# v1_0.net
KiCad netlist of a schematic drawn in Altium Designer
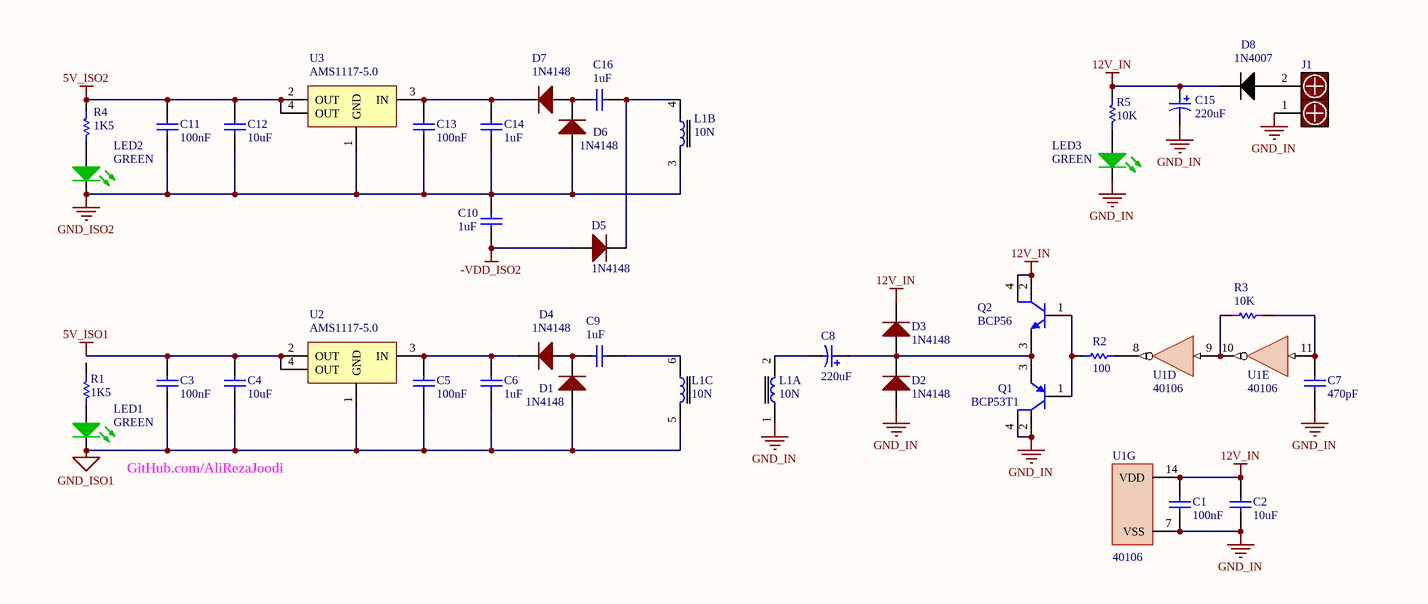
[diagram p0: v1.0.SchDoc]

(export (version "E")
  (design (tool "Eeschema 10.0.6"))
  (components
    (comp (ref "C1")
      (value "100nF")
      (footprint "Capacitor_Ceramic:SMD_0805")
      (description "Capacitor, Ceramic Multilayer, 25V, 10%")
      (libsource (lib "General") (part "Capacitor_Ceramic"))
    )
    (comp (ref "C2")
      (value "10uF")
      (footprint "Capacitor_Ceramic:SMD_0805")
      (description "Capacitor, Ceramic Multilayer, 25V, 10%")
      (libsource (lib "General") (part "Capacitor_Ceramic"))
    )
    (comp (ref "C3")
      (value "100nF")
      (footprint "Capacitor_Ceramic:SMD_0805")
      (description "Capacitor, Ceramic Multilayer, 25V, 10%")
      (libsource (lib "General") (part "Capacitor_Ceramic"))
    )
    (comp (ref "C4")
      (value "10uF")
      (footprint "Capacitor_Ceramic:SMD_0805")
      (description "Capacitor, Ceramic Multilayer, 25V, 10%")
      (libsource (lib "General") (part "Capacitor_Ceramic"))
    )
    (comp (ref "C5")
      (value "100nF")
      (footprint "Capacitor_Ceramic:SMD_0805")
      (description "Capacitor, Ceramic Multilayer, 25V, 10%")
      (libsource (lib "General") (part "Capacitor_Ceramic"))
    )
    (comp (ref "C6")
      (value "1uF")
      (footprint "Capacitor_Ceramic:SMD_0805")
      (description "Capacitor, Ceramic Multilayer, 25V, 10%")
      (libsource (lib "General") (part "Capacitor_Ceramic"))
    )
    (comp (ref "C7")
      (value "470pF")
      (footprint "Capacitor_Ceramic:SMD_0805")
      (description "Capacitor, Ceramic Multilayer, 25V, 10%")
      (libsource (lib "General") (part "Capacitor_Ceramic"))
    )
    (comp (ref "C8")
      (value "220uF")
      (footprint "THD_P3.4/D8/H12")
      (description "Capacitor, Electrolytic, 25V, 10%")
      (libsource (lib "General") (part "Capacitor_Electrolytic"))
    )
    (comp (ref "C9")
      (value "1uF")
      (footprint "Capacitor_Ceramic:SMD_0805")
      (description "Capacitor, Ceramic Multilayer, 25V, 10%")
      (libsource (lib "General") (part "Capacitor_Ceramic"))
    )
    (comp (ref "C10")
      (value "1uF")
      (footprint "Capacitor_Ceramic:SMD_0805")
      (description "Capacitor, Ceramic Multilayer, 25V, 10%")
      (libsource (lib "General") (part "Capacitor_Ceramic"))
    )
    (comp (ref "C11")
      (value "100nF")
      (footprint "Capacitor_Ceramic:SMD_0805")
      (description "Capacitor, Ceramic Multilayer, 25V, 10%")
      (libsource (lib "General") (part "Capacitor_Ceramic"))
    )
    (comp (ref "C12")
      (value "10uF")
      (footprint "Capacitor_Ceramic:SMD_0805")
      (description "Capacitor, Ceramic Multilayer, 25V, 10%")
      (libsource (lib "General") (part "Capacitor_Ceramic"))
    )
    (comp (ref "C13")
      (value "100nF")
      (footprint "Capacitor_Ceramic:SMD_0805")
      (description "Capacitor, Ceramic Multilayer, 25V, 10%")
      (libsource (lib "General") (part "Capacitor_Ceramic"))
    )
    (comp (ref "C14")
      (value "1uF")
      (footprint "Capacitor_Ceramic:SMD_0805")
      (description "Capacitor, Ceramic Multilayer, 25V, 10%")
      (libsource (lib "General") (part "Capacitor_Ceramic"))
    )
    (comp (ref "C15")
      (value "220uF")
      (footprint "THD_P3.4/D8/H12")
      (description "Capacitor, Electrolytic, 25V, 10%")
      (libsource (lib "General") (part "Capacitor_Electrolytic"))
    )
    (comp (ref "C16")
      (value "1uF")
      (footprint "Capacitor_Ceramic:SMD_0805")
      (description "Capacitor, Ceramic Multilayer, 25V, 10%")
      (libsource (lib "General") (part "Capacitor_Ceramic"))
    )
    (comp (ref "D1")
      (value "1N4148")
      (footprint "SMD_DO-213AA")
      (description "Diode")
      (fields (field (name "MANUFACTURER") "Microchip Technology") (field (name "PART NUMBER") "1N4148UR-1"))
      (libsource (lib "General") (part "Diode_2Form"))
    )
    (comp (ref "D2")
      (value "1N4148")
      (footprint "SMD_DO-213AA")
      (description "Diode")
      (fields (field (name "MANUFACTURER") "Microchip Technology") (field (name "PART NUMBER") "1N4148UR-1"))
      (libsource (lib "General") (part "Diode_2Form"))
    )
    (comp (ref "D3")
      (value "1N4148")
      (footprint "SMD_DO-213AA")
      (description "Diode")
      (fields (field (name "MANUFACTURER") "Microchip Technology") (field (name "PART NUMBER") "1N4148UR-1"))
      (libsource (lib "General") (part "Diode_2Form"))
    )
    (comp (ref "D4")
      (value "1N4148")
      (footprint "SMD_DO-213AA")
      (description "Diode")
      (fields (field (name "MANUFACTURER") "Microchip Technology") (field (name "PART NUMBER") "1N4148UR-1"))
      (libsource (lib "General") (part "Diode_2Form"))
    )
    (comp (ref "D5")
      (value "1N4148")
      (footprint "SMD_DO-213AA")
      (description "Diode")
      (fields (field (name "MANUFACTURER") "Microchip Technology") (field (name "PART NUMBER") "1N4148UR-1"))
      (libsource (lib "General") (part "Diode_2Form"))
    )
    (comp (ref "D6")
      (value "1N4148")
      (footprint "SMD_DO-213AA")
      (description "Diode")
      (fields (field (name "MANUFACTURER") "Microchip Technology") (field (name "PART NUMBER") "1N4148UR-1"))
      (libsource (lib "General") (part "Diode_2Form"))
    )
    (comp (ref "D7")
      (value "1N4148")
      (footprint "SMD_DO-213AA")
      (description "Diode")
      (fields (field (name "MANUFACTURER") "Microchip Technology") (field (name "PART NUMBER") "1N4148UR-1"))
      (libsource (lib "General") (part "Diode_2Form"))
    )
    (comp (ref "D8")
      (value "1N4007")
      (footprint "SMD_SOD123W")
      (description "Diode")
      (fields (field (name "MANUFACTURER") "SMC Diode Solutions") (field (name "PART NUMBER") "1N4007FL"))
      (libsource (lib "General") (part "Diode"))
    )
    (comp (ref "J1")
      (value "~")
      (footprint "1x2_P8.26")
      (description "Connector, Barrier Terminal Blocks, 2Pin")
      (fields (field (name "1_PART NUMBER") "1977477-2"))
      (libsource (lib "Connector") (part "Connector1x2_Power_4Form"))
    )
    (comp (ref "L1")
      (value "10N")
      (footprint "TOROIDS_DO25/DI15/L13")
      (description "Power Transformer, Ferrite Toroids")
      (fields (field (name "MANUFACTURER") "TDK") (field (name "PART NUMBER") "HF70T25X13X15"))
      (libsource (lib "") (part "Inductor_Trans_3Wire_2Form_1"))
    )
    (comp (ref "LED1")
      (value "GREEN")
      (footprint "SMD_0805_GREEN")
      (description "LED")
      (libsource (lib "Display") (part "LED_GREEN"))
    )
    (comp (ref "LED2")
      (value "GREEN")
      (footprint "SMD_0805_GREEN")
      (description "LED")
      (libsource (lib "Display") (part "LED_GREEN"))
    )
    (comp (ref "LED3")
      (value "GREEN")
      (footprint "SMD_0805_GREEN")
      (description "LED")
      (libsource (lib "Display") (part "LED_GREEN"))
    )
    (comp (ref "Q1")
      (value "BCP53T1")
      (footprint "SOT223_4PIN")
      (description "Transistor, BJT, PNP")
      (fields (field (name "MANUFACTURER") "ON Semiconductor") (field (name "PART NUMBER") "BCP53T1G"))
      (libsource (lib "General") (part "Transistor_BJT_PNP_bcec"))
    )
    (comp (ref "Q2")
      (value "BCP56")
      (footprint "SOT223_4PIN")
      (description "Transistor, BJT, NPN")
      (fields (field (name "PART NUMBER") "BCP56-16T1G") (field (name "MANUFACTURER") "ON Semiconductor"))
      (libsource (lib "General") (part "Transistor_BJT_NPN_bcec"))
    )
    (comp (ref "R1")
      (value "1K5")
      (footprint "SMD_0805")
      (description "Resistor, 1/8W, 5%")
      (libsource (lib "General") (part "Resistor"))
    )
    (comp (ref "R2")
      (value "100")
      (footprint "SMD_0805")
      (description "Resistor, 1/8W, 5%")
      (fields (field (name "TOLERANCE") "5%") (field (name "POWER") "1/8W"))
      (libsource (lib "General") (part "Resistor"))
    )
    (comp (ref "R3")
      (value "10K")
      (footprint "SMD_0805")
      (description "Resistor, 1/8W, 5%")
      (libsource (lib "") (part "Resistor_1"))
    )
    (comp (ref "R4")
      (value "1K5")
      (footprint "SMD_0805")
      (description "Resistor, 1/8W, 5%")
      (libsource (lib "General") (part "Resistor"))
    )
    (comp (ref "R5")
      (value "10K")
      (footprint "SMD_0805")
      (description "Resistor, 1/8W, 5%")
      (libsource (lib "General") (part "Resistor"))
    )
    (comp (ref "U1")
      (value "40106")
      (footprint "SOIC127P600X175-14N")
      (description "Hex inverting Schmitt trigger")
      (fields (field (name "MANUFACTURER") "Texas Instruments") (field (name "PART NUMBER") "CD40106BM96"))
      (libsource (lib "IC") (part "40106"))
    )
    (comp (ref "U2")
      (value "AMS1117-5.0")
      (footprint "SOT223_4PIN")
      (description "Low Dropout Linear Regulator")
      (fields
        (field (name "PART NUMBER") "LM1117IMP-5.0/NOPB")
        (field (name "MANUFACTURER") "Texas Instruments")
      )
      (libsource (lib "IC") (part "AMS1117"))
    )
    (comp (ref "U3")
      (value "AMS1117-5.0")
      (footprint "SOT223_4PIN")
      (description "Low Dropout Linear Regulator")
      (fields
        (field (name "MANUFACTURER") "Texas Instruments")
        (field (name "PART NUMBER") "LM1117IMP-5.0/NOPB")
      )
      (libsource (lib "IC") (part "AMS1117"))
    )
  )
  (nets
    (net (code "1") (name "-VDD_ISO2") (class "Default")
      (node (ref "C10") (pin "1") (pinfunction "1_1") (pintype "passive"))
      (node (ref "D5") (pin "1") (pinfunction "A_1") (pintype "passive"))
    )
    (net (code "2") (name "5V_ISO1") (class "Default")
      (node (ref "C3") (pin "1") (pinfunction "1_1") (pintype "passive"))
      (node (ref "C4") (pin "1") (pinfunction "1_1") (pintype "passive"))
      (node (ref "U2") (pin "2") (pinfunction "OUT_2") (pintype "power_in"))
      (node (ref "U2") (pin "4") (pinfunction "OUT_4") (pintype "power_in"))
    )
    (net (code "3") (name "5V_ISO2") (class "Default")
      (node (ref "C11") (pin "1") (pinfunction "1_1") (pintype "passive"))
      (node (ref "C12") (pin "1") (pinfunction "1_1") (pintype "passive"))
      (node (ref "R4") (pin "2") (pinfunction "2_2") (pintype "passive"))
      (node (ref "U3") (pin "2") (pinfunction "OUT_2") (pintype "power_in"))
      (node (ref "U3") (pin "4") (pinfunction "OUT_4") (pintype "power_in"))
    )
    (net (code "4") (name "12V_IN") (class "Default")
      (node (ref "C1") (pin "2") (pinfunction "2_2") (pintype "passive"))
      (node (ref "C15") (pin "1") (pinfunction "1_1") (pintype "passive"))
      (node (ref "C2") (pin "1") (pinfunction "1_1") (pintype "passive"))
      (node (ref "D3") (pin "2") (pinfunction "K_2") (pintype "passive"))
      (node (ref "D8") (pin "2") (pinfunction "K_2") (pintype "passive"))
      (node (ref "Q2") (pin "2") (pinfunction "C_2") (pintype "passive"))
      (node (ref "Q2") (pin "4") (pinfunction "C_4") (pintype "passive"))
      (node (ref "R5") (pin "2") (pinfunction "2_2") (pintype "passive"))
      (node (ref "U1") (pin "14") (pinfunction "VDD_14") (pintype "passive"))
    )
    (net (code "5") (name "GND_IN") (class "Default")
      (node (ref "C1") (pin "1") (pinfunction "1_1") (pintype "passive"))
      (node (ref "C15") (pin "2") (pinfunction "2_2") (pintype "passive"))
      (node (ref "C2") (pin "2") (pinfunction "2_2") (pintype "passive"))
      (node (ref "C7") (pin "1") (pinfunction "1_1") (pintype "passive"))
      (node (ref "D2") (pin "1") (pinfunction "A_1") (pintype "passive"))
      (node (ref "J1") (pin "1") (pinfunction "1_1") (pintype "passive"))
      (node (ref "L1") (pin "1") (pinfunction "1_1") (pintype "passive"))
      (node (ref "LED3") (pin "2") (pinfunction "K_2") (pintype "passive"))
      (node (ref "Q1") (pin "2") (pinfunction "C_2") (pintype "passive"))
      (node (ref "Q1") (pin "4") (pinfunction "E_4") (pintype "passive"))
      (node (ref "U1") (pin "7") (pinfunction "VSS_7") (pintype "power_in"))
    )
    (net (code "6") (name "GND_ISO1") (class "Default")
      (node (ref "C3") (pin "2") (pinfunction "2_2") (pintype "passive"))
      (node (ref "C4") (pin "2") (pinfunction "2_2") (pintype "passive"))
      (node (ref "C5") (pin "2") (pinfunction "2_2") (pintype "passive"))
      (node (ref "C6") (pin "2") (pinfunction "2_2") (pintype "passive"))
      (node (ref "D1") (pin "1") (pinfunction "A_1") (pintype "passive"))
      (node (ref "L1") (pin "5") (pinfunction "5_5") (pintype "passive"))
      (node (ref "LED1") (pin "2") (pinfunction "K_2") (pintype "passive"))
      (node (ref "U2") (pin "1") (pinfunction "GND_1") (pintype "power_in"))
    )
    (net (code "7") (name "GND_ISO2") (class "Default")
      (node (ref "C10") (pin "2") (pinfunction "2_2") (pintype "passive"))
      (node (ref "C11") (pin "2") (pinfunction "2_2") (pintype "passive"))
      (node (ref "C12") (pin "2") (pinfunction "2_2") (pintype "passive"))
      (node (ref "C13") (pin "2") (pinfunction "2_2") (pintype "passive"))
      (node (ref "C14") (pin "2") (pinfunction "2_2") (pintype "passive"))
      (node (ref "D6") (pin "1") (pinfunction "A_1") (pintype "passive"))
      (node (ref "L1") (pin "3") (pinfunction "3_3") (pintype "passive"))
      (node (ref "LED2") (pin "2") (pinfunction "K_2") (pintype "passive"))
      (node (ref "U3") (pin "1") (pinfunction "GND_1") (pintype "power_in"))
    )
    (net (code "8") (name "Net-(C8-Pad2)") (class "Default")
      (node (ref "C8") (pin "2") (pinfunction "2_2") (pintype "passive"))
      (node (ref "L1") (pin "2") (pinfunction "2_2") (pintype "passive"))
    )
    (net (code "9") (name "Net-(C9-Pad1)") (class "Default")
      (node (ref "C9") (pin "1") (pinfunction "1_1") (pintype "passive"))
      (node (ref "L1") (pin "6") (pinfunction "6_6") (pintype "passive"))
    )
    (net (code "10") (name "Net-(D1-K)") (class "Default")
      (node (ref "C9") (pin "2") (pinfunction "2_2") (pintype "passive"))
      (node (ref "D1") (pin "2") (pinfunction "K_2") (pintype "passive"))
      (node (ref "D4") (pin "1") (pinfunction "A_1") (pintype "passive"))
    )
    (net (code "11") (name "Net-(D2-K)") (class "Default")
      (node (ref "C8") (pin "1") (pinfunction "1_1") (pintype "passive"))
      (node (ref "D2") (pin "2") (pinfunction "K_2") (pintype "passive"))
      (node (ref "D3") (pin "1") (pinfunction "A_1") (pintype "passive"))
      (node (ref "Q1") (pin "3") (pinfunction "E_3") (pintype "passive"))
      (node (ref "Q2") (pin "3") (pinfunction "E_3") (pintype "passive"))
    )
    (net (code "12") (name "Net-(D4-K)") (class "Default")
      (node (ref "C5") (pin "1") (pinfunction "1_1") (pintype "passive"))
      (node (ref "C6") (pin "1") (pinfunction "1_1") (pintype "passive"))
      (node (ref "D4") (pin "2") (pinfunction "K_2") (pintype "passive"))
      (node (ref "U2") (pin "3") (pinfunction "IN_3") (pintype "power_in"))
    )
    (net (code "13") (name "Net-(D5-K)") (class "Default")
      (node (ref "C16") (pin "1") (pinfunction "1_1") (pintype "passive"))
      (node (ref "D5") (pin "2") (pinfunction "K_2") (pintype "passive"))
      (node (ref "L1") (pin "4") (pinfunction "4_4") (pintype "passive"))
    )
    (net (code "14") (name "Net-(D6-K)") (class "Default")
      (node (ref "C16") (pin "2") (pinfunction "2_2") (pintype "passive"))
      (node (ref "D6") (pin "2") (pinfunction "K_2") (pintype "passive"))
      (node (ref "D7") (pin "1") (pinfunction "A_1") (pintype "passive"))
    )
    (net (code "15") (name "Net-(D7-K)") (class "Default")
      (node (ref "C13") (pin "1") (pinfunction "1_1") (pintype "passive"))
      (node (ref "C14") (pin "1") (pinfunction "1_1") (pintype "passive"))
      (node (ref "D7") (pin "2") (pinfunction "K_2") (pintype "passive"))
      (node (ref "U3") (pin "3") (pinfunction "IN_3") (pintype "power_in"))
    )
    (net (code "16") (name "Net-(D8-A)") (class "Default")
      (node (ref "D8") (pin "1") (pinfunction "A_1") (pintype "passive"))
      (node (ref "J1") (pin "2") (pinfunction "2_2") (pintype "passive"))
    )
    (net (code "17") (name "Net-(LED2-A)") (class "Default")
      (node (ref "LED2") (pin "1") (pinfunction "A_1") (pintype "passive"))
      (node (ref "R4") (pin "1") (pinfunction "1_1") (pintype "passive"))
    )
    (net (code "18") (name "Net-(LED3-A)") (class "Default")
      (node (ref "LED3") (pin "1") (pinfunction "A_1") (pintype "passive"))
      (node (ref "R5") (pin "1") (pinfunction "1_1") (pintype "passive"))
    )
    (net (code "19") (name "Net-(Q1-B)") (class "Default")
      (node (ref "Q1") (pin "1") (pinfunction "B_1") (pintype "passive"))
      (node (ref "Q2") (pin "1") (pinfunction "B_1") (pintype "passive"))
      (node (ref "R2") (pin "1") (pinfunction "1_1") (pintype "passive"))
    )
    (net (code "20") (name "Net-(U1D-I)") (class "Default")
      (node (ref "R3") (pin "2") (pinfunction "2_2") (pintype "passive"))
      (node (ref "U1") (pin "10") (pinfunction "~{O}_10") (pintype "output"))
      (node (ref "U1") (pin "9") (pinfunction "I_9") (pintype "input"))
    )
    (net (code "21") (name "Net-(U1D-~{O})") (class "Default")
      (node (ref "R2") (pin "2") (pinfunction "2_2") (pintype "passive"))
      (node (ref "U1") (pin "8") (pinfunction "~{O}_8") (pintype "output"))
    )
    (net (code "22") (name "Net-(U1E-I)") (class "Default")
      (node (ref "C7") (pin "2") (pinfunction "2_2") (pintype "passive"))
      (node (ref "R3") (pin "1") (pinfunction "1_1") (pintype "passive"))
      (node (ref "U1") (pin "11") (pinfunction "I_11") (pintype "input"))
    )
    (net (code "23") (name "unconnected-(LED1-A-Pad1)") (class "Default")
      (node (ref "LED1") (pin "1") (pinfunction "A_1") (pintype "passive"))
    )
    (net (code "24") (name "unconnected-(R1-Pad1)") (class "Default")
      (node (ref "R1") (pin "1") (pinfunction "1_1") (pintype "passive"))
    )
    (net (code "25") (name "unconnected-(R1-Pad2)") (class "Default")
      (node (ref "R1") (pin "2") (pinfunction "2_2") (pintype "passive"))
    )
  )
)
